# TMR_RAD_COMPARE.net
KiCad netlist of a schematic drawn in Altium Designer
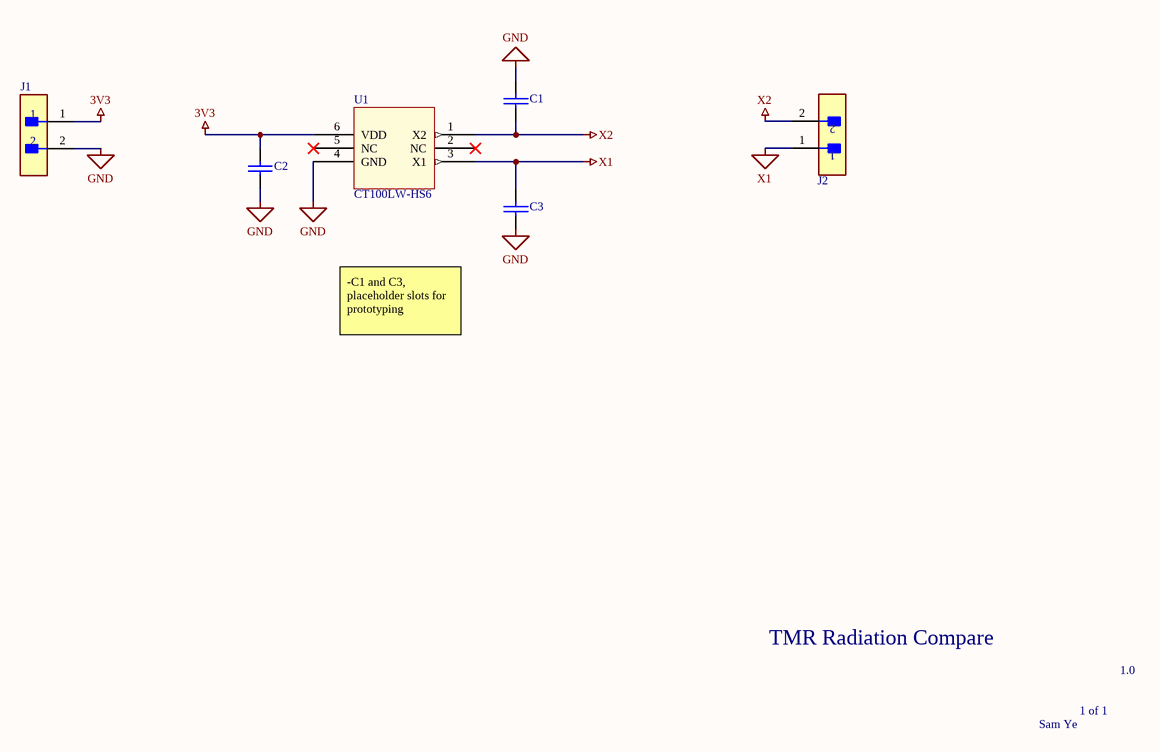
[diagram p0: TMR_RAD_COMPARE.SchDoc]

(export (version "E")
  (design (tool "Eeschema 10.0.6"))
  (components
    (comp (ref "C1")
      (value "*")
      (footprint "0805 CAP")
      (description "SMT ceramic capacitor 0805 size")
      (libsource (lib "EE209_SchLib") (part "CerCap_SMT_0805"))
    )
    (comp (ref "C2")
      (value "*")
      (footprint "0805 CAP")
      (description "SMT ceramic capacitor 0805 size")
      (libsource (lib "EE209_SchLib") (part "CerCap_SMT_0805"))
    )
    (comp (ref "C3")
      (value "*")
      (footprint "0805 CAP")
      (description "SMT ceramic capacitor 0805 size")
      (libsource (lib "EE209_SchLib") (part "CerCap_SMT_0805"))
    )
    (comp (ref "J1")
      (value "M20-9990245")
      (footprint "FP-M20-9990245-MFG")
      (description "CONN HEADER VERT 2POS 2.54MM")
      (fields (field (name "VOLTAGE") "50V"))
      (libsource (lib "") (part "CMP-15831-000105-1_1"))
    )
    (comp (ref "J2")
      (value "M20-9990245")
      (footprint "FP-M20-9990245-MFG")
      (description "CONN HEADER VERT 2POS 2.54MM")
      (fields (field (name "VOLTAGE") "50V"))
      (libsource (lib "male_headers") (part "CMP-15831-000105-1"))
    )
    (comp (ref "U1")
      (value "CT100LW-HS6")
      (footprint "CT100LW-HS6-Footprint-1")
      (description "Magnetoresistive Sensor, -50mT Min, 50mT Max, -1.43-1.43V, Rectangular, 6 Pin, Surface Mount")
      (libsource (lib "ECSE@UoA") (part "CT100LW-HS6-Symbol-1"))
    )
  )
  (nets
    (net (code "1") (name "3V3") (class "Default")
      (node (ref "C2") (pin "1") (pinfunction "1_1") (pintype "passive"))
      (node (ref "J1") (pin "1") (pinfunction "1_1") (pintype "passive"))
      (node (ref "U1") (pin "6") (pinfunction "VDD_6") (pintype "power_in"))
    )
    (net (code "2") (name "GND") (class "Default")
      (node (ref "C1") (pin "1") (pinfunction "1_1") (pintype "passive"))
      (node (ref "C2") (pin "2") (pinfunction "2_2") (pintype "passive"))
      (node (ref "C3") (pin "2") (pinfunction "2_2") (pintype "passive"))
      (node (ref "J1") (pin "2") (pinfunction "2_2") (pintype "passive"))
      (node (ref "U1") (pin "4") (pinfunction "GND_4") (pintype "power_in"))
    )
    (net (code "3") (name "X1") (class "Default")
      (node (ref "C3") (pin "1") (pinfunction "1_1") (pintype "passive"))
      (node (ref "J2") (pin "1") (pinfunction "1_1") (pintype "passive"))
      (node (ref "U1") (pin "3") (pinfunction "X1_3") (pintype "output"))
    )
    (net (code "4") (name "X2") (class "Default")
      (node (ref "C1") (pin "2") (pinfunction "2_2") (pintype "passive"))
      (node (ref "J2") (pin "2") (pinfunction "2_2") (pintype "passive"))
      (node (ref "U1") (pin "1") (pinfunction "X2_1") (pintype "output"))
    )
    (net (code "5") (name "unconnected-(U1-NC-Pad2)") (class "Default")
      (node (ref "U1") (pin "2") (pinfunction "NC_2") (pintype "passive+no_connect"))
    )
    (net (code "6") (name "unconnected-(U1-NC-Pad5)") (class "Default")
      (node (ref "U1") (pin "5") (pinfunction "NC_5") (pintype "passive+no_connect"))
    )
  )
)
